# dimmer3.net
KiCad netlist of a schematic drawn in EAGLE
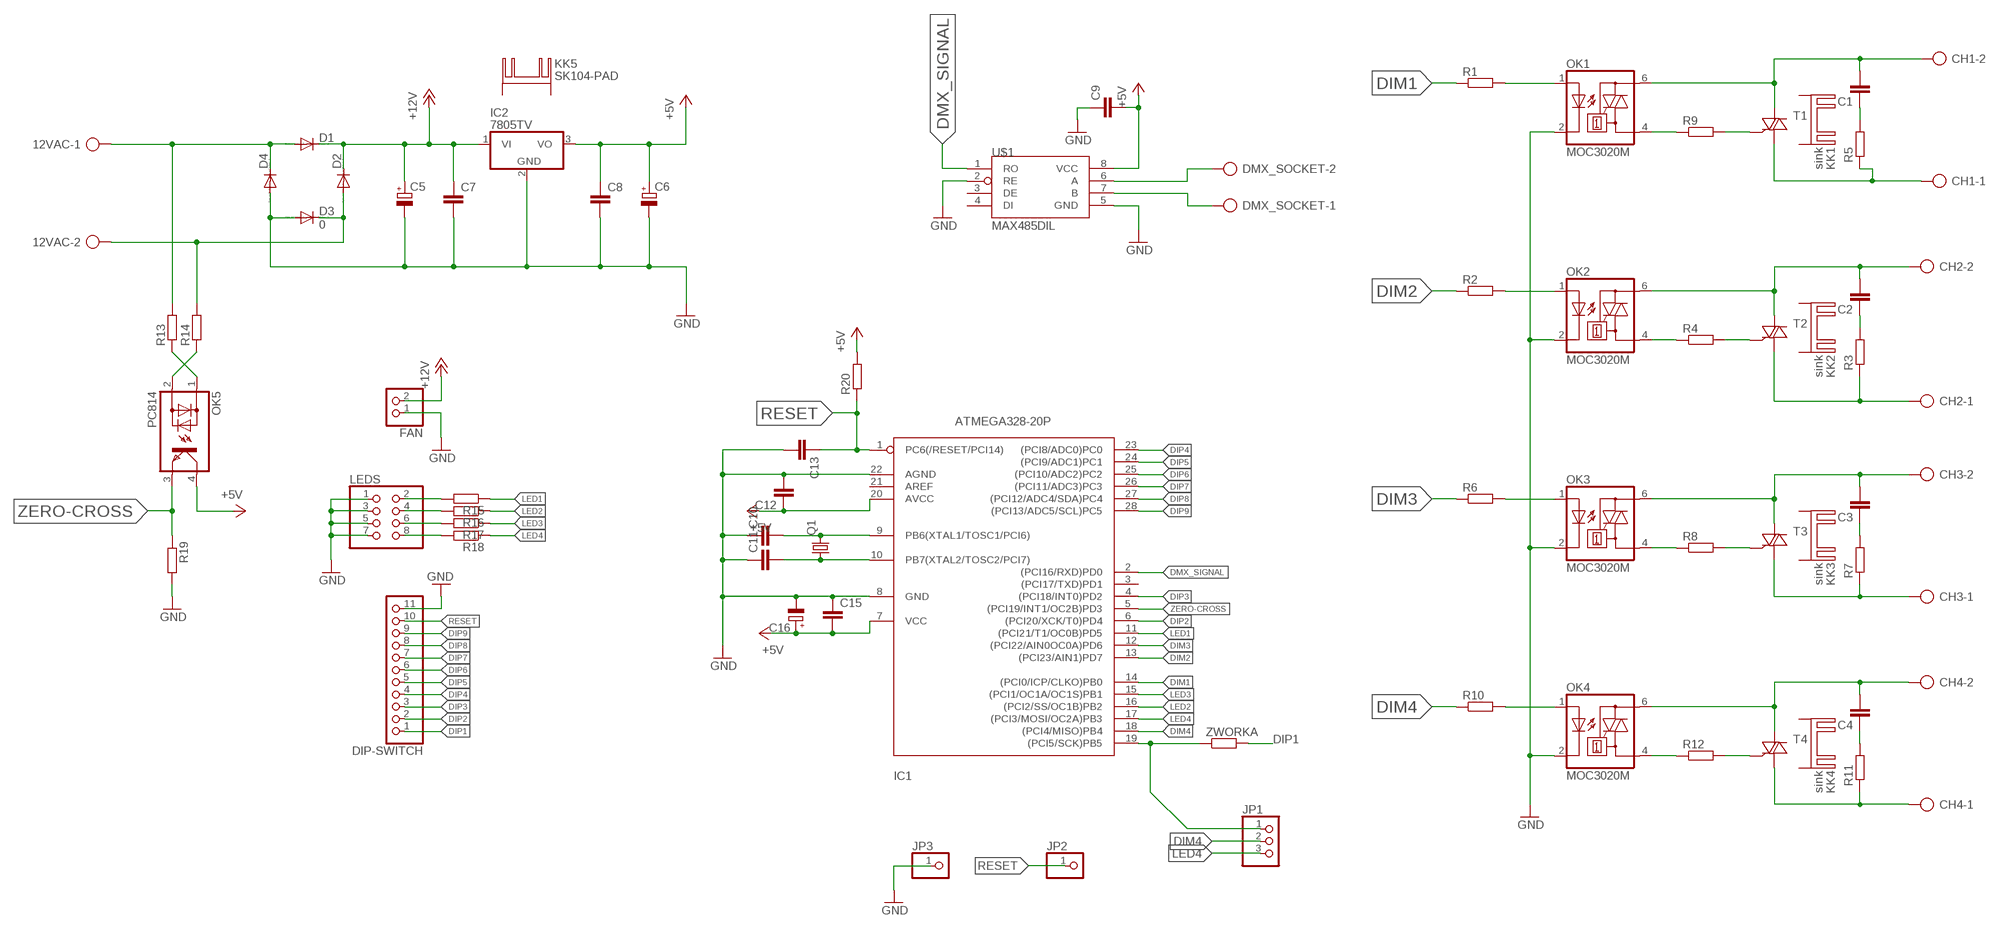
[diagram p0: schematic, sheet 1]

(export (version "E")
  (design (tool "Eeschema 10.0.6"))
  (components
    (comp (ref "12VAC")
      (value "AK500/2")
      (footprint "eagle-import:AK500_2")
      (libsource (lib "eagle-import") (part "AK500/2"))
    )
    (comp (ref "C1")
      (value "C-EU102-054X133")
      (footprint "eagle-import:C102-054X133")
      (libsource (lib "eagle-import") (part "C-EU102-054X133"))
    )
    (comp (ref "C2")
      (value "C-EU102-054X133")
      (footprint "eagle-import:C102-054X133")
      (libsource (lib "eagle-import") (part "C-EU102-054X133"))
    )
    (comp (ref "C3")
      (value "C-EU102-054X133")
      (footprint "eagle-import:C102-054X133")
      (libsource (lib "eagle-import") (part "C-EU102-054X133"))
    )
    (comp (ref "C4")
      (value "C-EU102-054X133")
      (footprint "eagle-import:C102-054X133")
      (libsource (lib "eagle-import") (part "C-EU102-054X133"))
    )
    (comp (ref "C5")
      (value "CPOL-EUE5-13")
      (footprint "eagle-import:E5-13")
      (libsource (lib "eagle-import") (part "CPOL-EUE5-13"))
    )
    (comp (ref "C6")
      (value "CPOL-EUE2.5-7")
      (footprint "eagle-import:E2,5-7")
      (libsource (lib "eagle-import") (part "CPOL-EUE2.5-7"))
    )
    (comp (ref "C7")
      (value "C-EU050-024X044")
      (footprint "eagle-import:C050-024X044")
      (libsource (lib "eagle-import") (part "C-EU050-024X044"))
    )
    (comp (ref "C8")
      (value "C-EU050-024X044")
      (footprint "eagle-import:C050-024X044")
      (libsource (lib "eagle-import") (part "C-EU050-024X044"))
    )
    (comp (ref "C9")
      (value "C-EU050-024X044")
      (footprint "eagle-import:C050-024X044")
      (libsource (lib "eagle-import") (part "C-EU050-024X044"))
    )
    (comp (ref "C10")
      (value "C-EU050-024X044")
      (footprint "eagle-import:C050-024X044")
      (libsource (lib "eagle-import") (part "C-EU050-024X044"))
    )
    (comp (ref "C11")
      (value "C-EU050-024X044")
      (footprint "eagle-import:C050-024X044")
      (libsource (lib "eagle-import") (part "C-EU050-024X044"))
    )
    (comp (ref "C12")
      (value "C-EU050-024X044")
      (footprint "eagle-import:C050-024X044")
      (libsource (lib "eagle-import") (part "C-EU050-024X044"))
    )
    (comp (ref "C13")
      (value "C-EU050-024X044")
      (footprint "eagle-import:C050-024X044")
      (libsource (lib "eagle-import") (part "C-EU050-024X044"))
    )
    (comp (ref "C15")
      (value "C-EU050-024X044")
      (footprint "eagle-import:C050-024X044")
      (libsource (lib "eagle-import") (part "C-EU050-024X044"))
    )
    (comp (ref "C16")
      (value "CPOL-EUE2,5-6E")
      (footprint "eagle-import:E2,5-6E")
      (libsource (lib "eagle-import") (part "CPOL-EUE2,5-6E"))
    )
    (comp (ref "CH1")
      (value "AK500/2")
      (footprint "eagle-import:AK500_2")
      (libsource (lib "eagle-import") (part "AK500/2"))
    )
    (comp (ref "CH2")
      (value "AK500/2")
      (footprint "eagle-import:AK500_2")
      (libsource (lib "eagle-import") (part "AK500/2"))
    )
    (comp (ref "CH3")
      (value "AK500/2")
      (footprint "eagle-import:AK500_2")
      (libsource (lib "eagle-import") (part "AK500/2"))
    )
    (comp (ref "CH4")
      (value "AK500/2")
      (footprint "eagle-import:AK500_2")
      (libsource (lib "eagle-import") (part "AK500/2"))
    )
    (comp (ref "D1")
      (value "1N4004")
      (footprint "eagle-import:DO41-10")
      (libsource (lib "eagle-import") (part "1N4004"))
    )
    (comp (ref "D2")
      (value "1N4004")
      (footprint "eagle-import:DO41-10")
      (libsource (lib "eagle-import") (part "1N4004"))
    )
    (comp (ref "D3")
      (value "0")
      (footprint "eagle-import:DO41-10")
      (libsource (lib "eagle-import") (part "1N4004"))
    )
    (comp (ref "D4")
      (value "1N4004")
      (footprint "eagle-import:DO41-10")
      (libsource (lib "eagle-import") (part "1N4004"))
    )
    (comp (ref "DIP-SWITCH")
      (value "PINHD-1X11")
      (footprint "eagle-import:1X11")
      (libsource (lib "eagle-import") (part "PINHD-1X11"))
    )
    (comp (ref "DMX_SOCKET")
      (value "AK500/2")
      (footprint "eagle-import:AK500_2")
      (libsource (lib "eagle-import") (part "AK500/2"))
    )
    (comp (ref "FAN")
      (value "PINHD-1X2")
      (footprint "eagle-import:1X02")
      (libsource (lib "eagle-import") (part "PINHD-1X2"))
    )
    (comp (ref "IC1")
      (value "ATMEGA328-20P")
      (footprint "eagle-import:DIL28-3")
      (libsource (lib "eagle-import") (part "ATMEGA328P-20"))
    )
    (comp (ref "IC2")
      (value "7805TV")
      (footprint "eagle-import:TO220V")
      (libsource (lib "eagle-import") (part "78TV05"))
    )
    (comp (ref "JP1")
      (value "PINHD-1X3")
      (footprint "eagle-import:1X03")
      (libsource (lib "eagle-import") (part "PINHD-1X3"))
    )
    (comp (ref "JP2")
      (value "PINHD-1X1")
      (footprint "eagle-import:1X01")
      (libsource (lib "eagle-import") (part "PINHD-1X1"))
    )
    (comp (ref "JP3")
      (value "PINHD-1X1")
      (footprint "eagle-import:1X01")
      (libsource (lib "eagle-import") (part "PINHD-1X1"))
    )
    (comp (ref "KK1")
      (value "sink")
      (footprint "eagle-import:SK104-PAD")
      (libsource (lib "eagle-import") (part "SK104-PAD"))
    )
    (comp (ref "KK2")
      (value "sink")
      (footprint "eagle-import:SK104-PAD")
      (libsource (lib "eagle-import") (part "SK104-PAD"))
    )
    (comp (ref "KK3")
      (value "sink")
      (footprint "eagle-import:SK104-PAD")
      (libsource (lib "eagle-import") (part "SK104-PAD"))
    )
    (comp (ref "KK4")
      (value "sink")
      (footprint "eagle-import:SK104-PAD")
      (libsource (lib "eagle-import") (part "SK104-PAD"))
    )
    (comp (ref "KK5")
      (value "SK104-PAD")
      (footprint "eagle-import:SK104-PAD")
      (libsource (lib "eagle-import") (part "SK104-PAD"))
    )
    (comp (ref "LEDS")
      (value "PINHD-2X4")
      (footprint "eagle-import:2X04")
      (libsource (lib "eagle-import") (part "PINHD-2X4"))
    )
    (comp (ref "OK1")
      (value "MOC3020M")
      (footprint "eagle-import:DIL06")
      (fields (field (name "MF") "FAIRCHILD SEMICONDUCTOR") (field (name "MPN") "MOC3020-M"))
      (libsource (lib "eagle-import") (part "MOC30M20"))
    )
    (comp (ref "OK2")
      (value "MOC3020M")
      (footprint "eagle-import:DIL06")
      (fields (field (name "MF") "FAIRCHILD SEMICONDUCTOR") (field (name "MPN") "MOC3020-M"))
      (libsource (lib "eagle-import") (part "MOC30M20"))
    )
    (comp (ref "OK3")
      (value "MOC3020M")
      (footprint "eagle-import:DIL06")
      (fields (field (name "MF") "FAIRCHILD SEMICONDUCTOR") (field (name "MPN") "MOC3020-M"))
      (libsource (lib "eagle-import") (part "MOC30M20"))
    )
    (comp (ref "OK4")
      (value "MOC3020M")
      (footprint "eagle-import:DIL06")
      (fields (field (name "MF") "FAIRCHILD SEMICONDUCTOR") (field (name "MPN") "MOC3020-M"))
      (libsource (lib "eagle-import") (part "MOC30M20"))
    )
    (comp (ref "OK5")
      (value "PC814")
      (footprint "eagle-import:DIL04")
      (libsource (lib "eagle-import") (part "PC814"))
    )
    (comp (ref "Q1")
      (value "CRYSTALHC49U-V")
      (footprint "eagle-import:HC49U-V")
      (libsource (lib "eagle-import") (part "CRYSTALHC49U-V"))
    )
    (comp (ref "R1")
      (value "R-EU_0207/10")
      (footprint "eagle-import:0207_10")
      (libsource (lib "eagle-import") (part "R-EU_0207/10"))
    )
    (comp (ref "R2")
      (value "R-EU_0207/10")
      (footprint "eagle-import:0207_10")
      (libsource (lib "eagle-import") (part "R-EU_0207/10"))
    )
    (comp (ref "R3")
      (value "R-EU_0617/22")
      (footprint "eagle-import:0617_22")
      (libsource (lib "eagle-import") (part "R-EU_0617/22"))
    )
    (comp (ref "R4")
      (value "R-EU_0207/10")
      (footprint "eagle-import:0207_10")
      (libsource (lib "eagle-import") (part "R-EU_0207/10"))
    )
    (comp (ref "R5")
      (value "R-EU_0617/22")
      (footprint "eagle-import:0617_22")
      (libsource (lib "eagle-import") (part "R-EU_0617/22"))
    )
    (comp (ref "R6")
      (value "R-EU_0207/10")
      (footprint "eagle-import:0207_10")
      (libsource (lib "eagle-import") (part "R-EU_0207/10"))
    )
    (comp (ref "R7")
      (value "R-EU_0617/22")
      (footprint "eagle-import:0617_22")
      (libsource (lib "eagle-import") (part "R-EU_0617/22"))
    )
    (comp (ref "R8")
      (value "R-EU_0207/10")
      (footprint "eagle-import:0207_10")
      (libsource (lib "eagle-import") (part "R-EU_0207/10"))
    )
    (comp (ref "R9")
      (value "R-EU_0207/10")
      (footprint "eagle-import:0207_10")
      (libsource (lib "eagle-import") (part "R-EU_0207/10"))
    )
    (comp (ref "R10")
      (value "R-EU_0207/10")
      (footprint "eagle-import:0207_10")
      (libsource (lib "eagle-import") (part "R-EU_0207/10"))
    )
    (comp (ref "R11")
      (value "R-EU_0617/22")
      (footprint "eagle-import:0617_22")
      (libsource (lib "eagle-import") (part "R-EU_0617/22"))
    )
    (comp (ref "R12")
      (value "R-EU_0207/10")
      (footprint "eagle-import:0207_10")
      (libsource (lib "eagle-import") (part "R-EU_0207/10"))
    )
    (comp (ref "R13")
      (value "R-EU_0207/10")
      (footprint "eagle-import:0207_10")
      (libsource (lib "eagle-import") (part "R-EU_0207/10"))
    )
    (comp (ref "R14")
      (value "R-EU_0207/10")
      (footprint "eagle-import:0207_10")
      (libsource (lib "eagle-import") (part "R-EU_0207/10"))
    )
    (comp (ref "R15")
      (value "R-EU_0207/10")
      (footprint "eagle-import:0207_10")
      (libsource (lib "eagle-import") (part "R-EU_0207/10"))
    )
    (comp (ref "R16")
      (value "R-EU_0207/10")
      (footprint "eagle-import:0207_10")
      (libsource (lib "eagle-import") (part "R-EU_0207/10"))
    )
    (comp (ref "R17")
      (value "R-EU_0207/10")
      (footprint "eagle-import:0207_10")
      (libsource (lib "eagle-import") (part "R-EU_0207/10"))
    )
    (comp (ref "R18")
      (value "R-EU_0207/10")
      (footprint "eagle-import:0207_10")
      (libsource (lib "eagle-import") (part "R-EU_0207/10"))
    )
    (comp (ref "R19")
      (value "R-EU_0207/10")
      (footprint "eagle-import:0207_10")
      (libsource (lib "eagle-import") (part "R-EU_0207/10"))
    )
    (comp (ref "R20")
      (value "R-EU_0207/10")
      (footprint "eagle-import:0207_10")
      (libsource (lib "eagle-import") (part "R-EU_0207/10"))
    )
    (comp (ref "T1")
      (value "BT138-DSH")
      (footprint "eagle-import:TO220DSH")
      (libsource (lib "eagle-import") (part "BT138-DSH"))
    )
    (comp (ref "T2")
      (value "BT138-DSH")
      (footprint "eagle-import:TO220DSH")
      (libsource (lib "eagle-import") (part "BT138-DSH"))
    )
    (comp (ref "T3")
      (value "BT138-DSH")
      (footprint "eagle-import:TO220DSH")
      (libsource (lib "eagle-import") (part "BT138-DSH"))
    )
    (comp (ref "T4")
      (value "BT138-DSH")
      (footprint "eagle-import:TO220DSH")
      (libsource (lib "eagle-import") (part "BT138-DSH"))
    )
    (comp (ref "U$1")
      (value "MAX485DIL")
      (footprint "eagle-import:DIL08")
      (libsource (lib "eagle-import") (part "MAX485DIL"))
    )
    (comp (ref "ZWORKA")
      (value "R-EU_0204/7")
      (footprint "eagle-import:0204_7")
      (libsource (lib "eagle-import") (part "R-EU_0204/7"))
    )
  )
  (nets
    (net (code "1") (name "+5V") (class "Default")
      (node (ref "C12") (pin "1") (pinfunction "1_1") (pintype "passive"))
      (node (ref "C15") (pin "2") (pinfunction "2_2") (pintype "passive"))
      (node (ref "C16") (pin "+") (pinfunction "+_+") (pintype "passive"))
      (node (ref "C6") (pin "+") (pinfunction "+_+") (pintype "passive"))
      (node (ref "C8") (pin "1") (pinfunction "1_1") (pintype "passive"))
      (node (ref "C9") (pin "2") (pinfunction "2_2") (pintype "passive"))
      (node (ref "IC1") (pin "20") (pinfunction "AVCC_20") (pintype "bidirectional"))
      (node (ref "IC1") (pin "7") (pinfunction "VCC_7") (pintype "bidirectional"))
      (node (ref "IC2") (pin "3") (pinfunction "VO_3") (pintype "passive"))
      (node (ref "OK5") (pin "4") (pinfunction "C_4") (pintype "passive"))
      (node (ref "R20") (pin "2") (pinfunction "2_2") (pintype "passive"))
      (node (ref "U$1") (pin "8") (pinfunction "VCC_8") (pintype "bidirectional"))
    )
    (net (code "2") (name "+12V") (class "Default")
      (node (ref "C5") (pin "+") (pinfunction "+_+") (pintype "passive"))
      (node (ref "C7") (pin "1") (pinfunction "1_1") (pintype "passive"))
      (node (ref "D1") (pin "C") (pinfunction "C_C") (pintype "passive"))
      (node (ref "D2") (pin "C") (pinfunction "C_C") (pintype "passive"))
      (node (ref "FAN") (pin "2") (pinfunction "2_2") (pintype "passive"))
      (node (ref "IC2") (pin "1") (pinfunction "VI_1") (pintype "input"))
    )
    (net (code "3") (name "DIM1") (class "Default")
      (node (ref "IC1") (pin "14") (pinfunction "(PCI0/ICP/CLKO)PB0_14") (pintype "bidirectional"))
      (node (ref "R1") (pin "1") (pinfunction "1_1") (pintype "passive"))
    )
    (net (code "4") (name "DIM2") (class "Default")
      (node (ref "IC1") (pin "13") (pinfunction "(PCI23/AIN1)PD7_13") (pintype "bidirectional"))
      (node (ref "R2") (pin "1") (pinfunction "1_1") (pintype "passive"))
    )
    (net (code "5") (name "DIM3") (class "Default")
      (node (ref "IC1") (pin "12") (pinfunction "(PCI22/AIN0OC0A)PD6_12") (pintype "bidirectional"))
      (node (ref "R6") (pin "1") (pinfunction "1_1") (pintype "passive"))
    )
    (net (code "6") (name "DIM4") (class "Default")
      (node (ref "IC1") (pin "18") (pinfunction "(PCI4/MISO)PB4_18") (pintype "bidirectional"))
      (node (ref "JP1") (pin "2") (pinfunction "2_2") (pintype "passive"))
      (node (ref "R10") (pin "1") (pinfunction "1_1") (pintype "passive"))
    )
    (net (code "7") (name "DIP1") (class "Default")
      (node (ref "DIP-SWITCH") (pin "1") (pinfunction "1_1") (pintype "passive"))
      (node (ref "ZWORKA") (pin "2") (pinfunction "2_2") (pintype "passive"))
    )
    (net (code "8") (name "DIP2") (class "Default")
      (node (ref "DIP-SWITCH") (pin "2") (pinfunction "2_2") (pintype "passive"))
      (node (ref "IC1") (pin "6") (pinfunction "(PCI20/XCK/T0)PD4_6") (pintype "bidirectional"))
    )
    (net (code "9") (name "DIP3") (class "Default")
      (node (ref "DIP-SWITCH") (pin "3") (pinfunction "3_3") (pintype "passive"))
      (node (ref "IC1") (pin "4") (pinfunction "(PCI18/INT0)PD2_4") (pintype "bidirectional"))
    )
    (net (code "10") (name "DIP4") (class "Default")
      (node (ref "DIP-SWITCH") (pin "4") (pinfunction "4_4") (pintype "passive"))
      (node (ref "IC1") (pin "23") (pinfunction "(PCI8/ADC0)PC0_23") (pintype "bidirectional"))
    )
    (net (code "11") (name "DIP5") (class "Default")
      (node (ref "DIP-SWITCH") (pin "5") (pinfunction "5_5") (pintype "passive"))
      (node (ref "IC1") (pin "24") (pinfunction "(PCI9/ADC1)PC1_24") (pintype "bidirectional"))
    )
    (net (code "12") (name "DIP6") (class "Default")
      (node (ref "DIP-SWITCH") (pin "6") (pinfunction "6_6") (pintype "passive"))
      (node (ref "IC1") (pin "25") (pinfunction "(PCI10/ADC2)PC2_25") (pintype "bidirectional"))
    )
    (net (code "13") (name "DIP7") (class "Default")
      (node (ref "DIP-SWITCH") (pin "7") (pinfunction "7_7") (pintype "passive"))
      (node (ref "IC1") (pin "26") (pinfunction "(PCI11/ADC3)PC3_26") (pintype "bidirectional"))
    )
    (net (code "14") (name "DIP8") (class "Default")
      (node (ref "DIP-SWITCH") (pin "8") (pinfunction "8_8") (pintype "passive"))
      (node (ref "IC1") (pin "27") (pinfunction "(PCI12/ADC4/SDA)PC4_27") (pintype "bidirectional"))
    )
    (net (code "15") (name "DIP9") (class "Default")
      (node (ref "DIP-SWITCH") (pin "9") (pinfunction "9_9") (pintype "passive"))
      (node (ref "IC1") (pin "28") (pinfunction "(PCI13/ADC5/SCL)PC5_28") (pintype "bidirectional"))
    )
    (net (code "16") (name "DMX_SIGNAL") (class "Default")
      (node (ref "IC1") (pin "2") (pinfunction "(PCI16/RXD)PD0_2") (pintype "bidirectional"))
      (node (ref "U$1") (pin "1") (pinfunction "RO_1") (pintype "bidirectional"))
    )
    (net (code "17") (name "GND") (class "Default")
      (node (ref "C10") (pin "1") (pinfunction "1_1") (pintype "passive"))
      (node (ref "C11") (pin "1") (pinfunction "1_1") (pintype "passive"))
      (node (ref "C12") (pin "2") (pinfunction "2_2") (pintype "passive"))
      (node (ref "C13") (pin "2") (pinfunction "2_2") (pintype "passive"))
      (node (ref "C15") (pin "1") (pinfunction "1_1") (pintype "passive"))
      (node (ref "C16") (pin "-") (pinfunction "-_-") (pintype "passive"))
      (node (ref "C5") (pin "-") (pinfunction "-_-") (pintype "passive"))
      (node (ref "C6") (pin "-") (pinfunction "-_-") (pintype "passive"))
      (node (ref "C7") (pin "2") (pinfunction "2_2") (pintype "passive"))
      (node (ref "C8") (pin "2") (pinfunction "2_2") (pintype "passive"))
      (node (ref "C9") (pin "1") (pinfunction "1_1") (pintype "passive"))
      (node (ref "D3") (pin "A") (pinfunction "A_A") (pintype "passive"))
      (node (ref "D4") (pin "A") (pinfunction "A_A") (pintype "passive"))
      (node (ref "DIP-SWITCH") (pin "11") (pinfunction "11_11") (pintype "passive"))
      (node (ref "FAN") (pin "1") (pinfunction "1_1") (pintype "passive"))
      (node (ref "IC1") (pin "22") (pinfunction "AGND_22") (pintype "bidirectional"))
      (node (ref "IC1") (pin "8") (pinfunction "GND_8") (pintype "bidirectional"))
      (node (ref "IC2") (pin "2") (pinfunction "GND_2") (pintype "passive"))
      (node (ref "JP3") (pin "1") (pinfunction "1_1") (pintype "passive"))
      (node (ref "LEDS") (pin "1") (pinfunction "1_1") (pintype "passive"))
      (node (ref "LEDS") (pin "3") (pinfunction "3_3") (pintype "passive"))
      (node (ref "LEDS") (pin "5") (pinfunction "5_5") (pintype "passive"))
      (node (ref "LEDS") (pin "7") (pinfunction "7_7") (pintype "passive"))
      (node (ref "OK1") (pin "2") (pinfunction "C_2") (pintype "passive"))
      (node (ref "OK2") (pin "2") (pinfunction "C_2") (pintype "passive"))
      (node (ref "OK3") (pin "2") (pinfunction "C_2") (pintype "passive"))
      (node (ref "OK4") (pin "2") (pinfunction "C_2") (pintype "passive"))
      (node (ref "R19") (pin "2") (pinfunction "2_2") (pintype "passive"))
      (node (ref "U$1") (pin "2") (pinfunction "RE_2") (pintype "bidirectional"))
      (node (ref "U$1") (pin "5") (pinfunction "GND_5") (pintype "bidirectional"))
    )
    (net (code "18") (name "LED1") (class "Default")
      (node (ref "IC1") (pin "11") (pinfunction "(PCI21/T1/OC0B)PD5_11") (pintype "bidirectional"))
      (node (ref "R15") (pin "1") (pinfunction "1_1") (pintype "passive"))
    )
    (net (code "19") (name "LED2") (class "Default")
      (node (ref "IC1") (pin "16") (pinfunction "(PCI2/SS/OC1B)PB2_16") (pintype "bidirectional"))
      (node (ref "R16") (pin "1") (pinfunction "1_1") (pintype "passive"))
    )
    (net (code "20") (name "LED3") (class "Default")
      (node (ref "IC1") (pin "15") (pinfunction "(PCI1/OC1A/OC1S)PB1_15") (pintype "bidirectional"))
      (node (ref "R17") (pin "1") (pinfunction "1_1") (pintype "passive"))
    )
    (net (code "21") (name "LED4") (class "Default")
      (node (ref "IC1") (pin "17") (pinfunction "(PCI3/MOSI/OC2A)PB3_17") (pintype "bidirectional"))
      (node (ref "JP1") (pin "3") (pinfunction "3_3") (pintype "passive"))
      (node (ref "R18") (pin "1") (pinfunction "1_1") (pintype "passive"))
    )
    (net (code "22") (name "Net-(12VACA-KL)") (class "Default")
      (node (ref "12VAC") (pin "1") (pinfunction "KL_1") (pintype "passive"))
      (node (ref "D1") (pin "A") (pinfunction "A_A") (pintype "passive"))
      (node (ref "D4") (pin "C") (pinfunction "C_C") (pintype "passive"))
      (node (ref "R13") (pin "2") (pinfunction "2_2") (pintype "passive"))
    )
    (net (code "23") (name "Net-(12VACB-KL)") (class "Default")
      (node (ref "12VAC") (pin "2") (pinfunction "KL_2") (pintype "passive"))
      (node (ref "D2") (pin "A") (pinfunction "A_A") (pintype "passive"))
      (node (ref "D3") (pin "C") (pinfunction "C_C") (pintype "passive"))
      (node (ref "R14") (pin "2") (pinfunction "2_2") (pintype "passive"))
    )
    (net (code "24") (name "Net-(C1-Pad1)") (class "Default")
      (node (ref "C1") (pin "1") (pinfunction "1_1") (pintype "passive"))
      (node (ref "R5") (pin "2") (pinfunction "2_2") (pintype "passive"))
    )
    (net (code "25") (name "Net-(C2-Pad1)") (class "Default")
      (node (ref "C2") (pin "1") (pinfunction "1_1") (pintype "passive"))
      (node (ref "R3") (pin "2") (pinfunction "2_2") (pintype "passive"))
    )
    (net (code "26") (name "Net-(C3-Pad1)") (class "Default")
      (node (ref "C3") (pin "1") (pinfunction "1_1") (pintype "passive"))
      (node (ref "R7") (pin "2") (pinfunction "2_2") (pintype "passive"))
    )
    (net (code "27") (name "Net-(C4-Pad1)") (class "Default")
      (node (ref "C4") (pin "1") (pinfunction "1_1") (pintype "passive"))
      (node (ref "R11") (pin "2") (pinfunction "2_2") (pintype "passive"))
    )
    (net (code "28") (name "Net-(CH1A-KL)") (class "Default")
      (node (ref "CH1") (pin "1") (pinfunction "KL_1") (pintype "passive"))
      (node (ref "R5") (pin "1") (pinfunction "1_1") (pintype "passive"))
      (node (ref "T1") (pin "A1") (pinfunction "A1_A1") (pintype "passive"))
    )
    (net (code "29") (name "Net-(CH1B-KL)") (class "Default")
      (node (ref "C1") (pin "2") (pinfunction "2_2") (pintype "passive"))
      (node (ref "CH1") (pin "2") (pinfunction "KL_2") (pintype "passive"))
      (node (ref "OK1") (pin "6") (pinfunction "A2_6") (pintype "passive"))
      (node (ref "T1") (pin "A2") (pinfunction "A2_A2") (pintype "passive"))
    )
    (net (code "30") (name "Net-(CH2A-KL)") (class "Default")
      (node (ref "CH2") (pin "1") (pinfunction "KL_1") (pintype "passive"))
      (node (ref "R3") (pin "1") (pinfunction "1_1") (pintype "passive"))
      (node (ref "T2") (pin "A1") (pinfunction "A1_A1") (pintype "passive"))
    )
    (net (code "31") (name "Net-(CH2B-KL)") (class "Default")
      (node (ref "C2") (pin "2") (pinfunction "2_2") (pintype "passive"))
      (node (ref "CH2") (pin "2") (pinfunction "KL_2") (pintype "passive"))
      (node (ref "OK2") (pin "6") (pinfunction "A2_6") (pintype "passive"))
      (node (ref "T2") (pin "A2") (pinfunction "A2_A2") (pintype "passive"))
    )
    (net (code "32") (name "Net-(CH3A-KL)") (class "Default")
      (node (ref "CH3") (pin "1") (pinfunction "KL_1") (pintype "passive"))
      (node (ref "R7") (pin "1") (pinfunction "1_1") (pintype "passive"))
      (node (ref "T3") (pin "A1") (pinfunction "A1_A1") (pintype "passive"))
    )
    (net (code "33") (name "Net-(CH3B-KL)") (class "Default")
      (node (ref "C3") (pin "2") (pinfunction "2_2") (pintype "passive"))
      (node (ref "CH3") (pin "2") (pinfunction "KL_2") (pintype "passive"))
      (node (ref "OK3") (pin "6") (pinfunction "A2_6") (pintype "passive"))
      (node (ref "T3") (pin "A2") (pinfunction "A2_A2") (pintype "passive"))
    )
    (net (code "34") (name "Net-(CH4A-KL)") (class "Default")
      (node (ref "CH4") (pin "1") (pinfunction "KL_1") (pintype "passive"))
      (node (ref "R11") (pin "1") (pinfunction "1_1") (pintype "passive"))
      (node (ref "T4") (pin "A1") (pinfunction "A1_A1") (pintype "passive"))
    )
    (net (code "35") (name "Net-(CH4B-KL)") (class "Default")
      (node (ref "C4") (pin "2") (pinfunction "2_2") (pintype "passive"))
      (node (ref "CH4") (pin "2") (pinfunction "KL_2") (pintype "passive"))
      (node (ref "OK4") (pin "6") (pinfunction "A2_6") (pintype "passive"))
      (node (ref "T4") (pin "A2") (pinfunction "A2_A2") (pintype "passive"))
    )
    (net (code "36") (name "Net-(DMX_SOCKETA-KL)") (class "Default")
      (node (ref "DMX_SOCKET") (pin "1") (pinfunction "KL_1") (pintype "passive"))
      (node (ref "U$1") (pin "7") (pinfunction "B_7") (pintype "bidirectional"))
    )
    (net (code "37") (name "Net-(DMX_SOCKETB-KL)") (class "Default")
      (node (ref "DMX_SOCKET") (pin "2") (pinfunction "KL_2") (pintype "passive"))
      (node (ref "U$1") (pin "6") (pinfunction "A_6") (pintype "bidirectional"))
    )
    (net (code "38") (name "Net-(IC1-(PCI5{slash}SCK)PB5)") (class "Default")
      (node (ref "IC1") (pin "19") (pinfunction "(PCI5/SCK)PB5_19") (pintype "bidirectional"))
      (node (ref "JP1") (pin "1") (pinfunction "1_1") (pintype "passive"))
      (node (ref "ZWORKA") (pin "1") (pinfunction "1_1") (pintype "passive"))
    )
    (net (code "39") (name "Net-(IC1-PB6(XTAL1{slash}TOSC1{slash}PCI6))") (class "Default")
      (node (ref "C10") (pin "2") (pinfunction "2_2") (pintype "passive"))
      (node (ref "IC1") (pin "9") (pinfunction "PB6(XTAL1/TOSC1/PCI6)_9") (pintype "bidirectional"))
      (node (ref "Q1") (pin "2") (pinfunction "2_2") (pintype "passive"))
    )
    (net (code "40") (name "Net-(IC1-PB7(XTAL2{slash}TOSC2{slash}PCI7))") (class "Default")
      (node (ref "C11") (pin "2") (pinfunction "2_2") (pintype "passive"))
      (node (ref "IC1") (pin "10") (pinfunction "PB7(XTAL2/TOSC2/PCI7)_10") (pintype "bidirectional"))
      (node (ref "Q1") (pin "1") (pinfunction "1_1") (pintype "passive"))
    )
    (net (code "41") (name "Net-(LEDS-Pad2)") (class "Default")
      (node (ref "LEDS") (pin "2") (pinfunction "2_2") (pintype "passive"))
      (node (ref "R15") (pin "2") (pinfunction "2_2") (pintype "passive"))
    )
    (net (code "42") (name "Net-(LEDS-Pad4)") (class "Default")
      (node (ref "LEDS") (pin "4") (pinfunction "4_4") (pintype "passive"))
      (node (ref "R16") (pin "2") (pinfunction "2_2") (pintype "passive"))
    )
    (net (code "43") (name "Net-(LEDS-Pad6)") (class "Default")
      (node (ref "LEDS") (pin "6") (pinfunction "6_6") (pintype "passive"))
      (node (ref "R17") (pin "2") (pinfunction "2_2") (pintype "passive"))
    )
    (net (code "44") (name "Net-(LEDS-Pad8)") (class "Default")
      (node (ref "LEDS") (pin "8") (pinfunction "8_8") (pintype "passive"))
      (node (ref "R18") (pin "2") (pinfunction "2_2") (pintype "passive"))
    )
    (net (code "45") (name "Net-(OK1-A)") (class "Default")
      (node (ref "OK1") (pin "1") (pinfunction "A_1") (pintype "passive"))
      (node (ref "R1") (pin "2") (pinfunction "2_2") (pintype "passive"))
    )
    (net (code "46") (name "Net-(OK1-A1)") (class "Default")
      (node (ref "OK1") (pin "4") (pinfunction "A1_4") (pintype "passive"))
      (node (ref "R9") (pin "1") (pinfunction "1_1") (pintype "passive"))
    )
    (net (code "47") (name "Net-(OK2-A)") (class "Default")
      (node (ref "OK2") (pin "1") (pinfunction "A_1") (pintype "passive"))
      (node (ref "R2") (pin "2") (pinfunction "2_2") (pintype "passive"))
    )
    (net (code "48") (name "Net-(OK2-A1)") (class "Default")
      (node (ref "OK2") (pin "4") (pinfunction "A1_4") (pintype "passive"))
      (node (ref "R4") (pin "1") (pinfunction "1_1") (pintype "passive"))
    )
    (net (code "49") (name "Net-(OK3-A)") (class "Default")
      (node (ref "OK3") (pin "1") (pinfunction "A_1") (pintype "passive"))
      (node (ref "R6") (pin "2") (pinfunction "2_2") (pintype "passive"))
    )
    (net (code "50") (name "Net-(OK3-A1)") (class "Default")
      (node (ref "OK3") (pin "4") (pinfunction "A1_4") (pintype "passive"))
      (node (ref "R8") (pin "1") (pinfunction "1_1") (pintype "passive"))
    )
    (net (code "51") (name "Net-(OK4-A)") (class "Default")
      (node (ref "OK4") (pin "1") (pinfunction "A_1") (pintype "passive"))
      (node (ref "R10") (pin "2") (pinfunction "2_2") (pintype "passive"))
    )
    (net (code "52") (name "Net-(OK4-A1)") (class "Default")
      (node (ref "OK4") (pin "4") (pinfunction "A1_4") (pintype "passive"))
      (node (ref "R12") (pin "1") (pinfunction "1_1") (pintype "passive"))
    )
    (net (code "53") (name "Net-(OK5-AC1)") (class "Default")
      (node (ref "OK5") (pin "1") (pinfunction "AC1_1") (pintype "passive"))
      (node (ref "R13") (pin "1") (pinfunction "1_1") (pintype "passive"))
    )
    (net (code "54") (name "Net-(OK5-AC2)") (class "Default")
      (node (ref "OK5") (pin "2") (pinfunction "AC2_2") (pintype "passive"))
      (node (ref "R14") (pin "1") (pinfunction "1_1") (pintype "passive"))
    )
    (net (code "55") (name "Net-(R4-Pad2)") (class "Default")
      (node (ref "R4") (pin "2") (pinfunction "2_2") (pintype "passive"))
      (node (ref "T2") (pin "G") (pinfunction "G_G") (pintype "passive"))
    )
    (net (code "56") (name "Net-(R8-Pad2)") (class "Default")
      (node (ref "R8") (pin "2") (pinfunction "2_2") (pintype "passive"))
      (node (ref "T3") (pin "G") (pinfunction "G_G") (pintype "passive"))
    )
    (net (code "57") (name "Net-(R9-Pad2)") (class "Default")
      (node (ref "R9") (pin "2") (pinfunction "2_2") (pintype "passive"))
      (node (ref "T1") (pin "G") (pinfunction "G_G") (pintype "passive"))
    )
    (net (code "58") (name "Net-(R12-Pad2)") (class "Default")
      (node (ref "R12") (pin "2") (pinfunction "2_2") (pintype "passive"))
      (node (ref "T4") (pin "G") (pinfunction "G_G") (pintype "passive"))
    )
    (net (code "59") (name "RESET") (class "Default")
      (node (ref "C13") (pin "1") (pinfunction "1_1") (pintype "passive"))
      (node (ref "DIP-SWITCH") (pin "10") (pinfunction "10_10") (pintype "passive"))
      (node (ref "IC1") (pin "1") (pinfunction "PC6(/RESET/PCI14)_1") (pintype "bidirectional"))
      (node (ref "JP2") (pin "1") (pinfunction "1_1") (pintype "passive"))
      (node (ref "R20") (pin "1") (pinfunction "1_1") (pintype "passive"))
    )
    (net (code "60") (name "ZERO-CROSS") (class "Default")
      (node (ref "IC1") (pin "5") (pinfunction "(PCI19/INT1/OC2B)PD3_5") (pintype "bidirectional"))
      (node (ref "OK5") (pin "3") (pinfunction "E_3") (pintype "passive"))
      (node (ref "R19") (pin "1") (pinfunction "1_1") (pintype "passive"))
    )
    (net (code "61") (name "unconnected-(IC1-(PCI17{slash}TXD)PD1-Pad3)") (class "Default")
      (node (ref "IC1") (pin "3") (pinfunction "(PCI17/TXD)PD1_3") (pintype "bidirectional"))
    )
    (net (code "62") (name "unconnected-(IC1-AREF-Pad21)") (class "Default")
      (node (ref "IC1") (pin "21") (pinfunction "AREF_21") (pintype "bidirectional"))
    )
    (net (code "63") (name "unconnected-(KK1-K-PadK1)") (class "Default")
      (node (ref "KK1") (pin "K1") (pinfunction "K_K1") (pintype "passive"))
    )
    (net (code "64") (name "unconnected-(KK1-K-PadK2)") (class "Default")
      (node (ref "KK1") (pin "K2") (pinfunction "K_K2") (pintype "passive"))
    )
    (net (code "65") (name "unconnected-(KK2-K-PadK1)") (class "Default")
      (node (ref "KK2") (pin "K1") (pinfunction "K_K1") (pintype "passive"))
    )
    (net (code "66") (name "unconnected-(KK2-K-PadK2)") (class "Default")
      (node (ref "KK2") (pin "K2") (pinfunction "K_K2") (pintype "passive"))
    )
    (net (code "67") (name "unconnected-(KK3-K-PadK1)") (class "Default")
      (node (ref "KK3") (pin "K1") (pinfunction "K_K1") (pintype "passive"))
    )
    (net (code "68") (name "unconnected-(KK3-K-PadK2)") (class "Default")
      (node (ref "KK3") (pin "K2") (pinfunction "K_K2") (pintype "passive"))
    )
    (net (code "69") (name "unconnected-(KK4-K-PadK1)") (class "Default")
      (node (ref "KK4") (pin "K1") (pinfunction "K_K1") (pintype "passive"))
    )
    (net (code "70") (name "unconnected-(KK4-K-PadK2)") (class "Default")
      (node (ref "KK4") (pin "K2") (pinfunction "K_K2") (pintype "passive"))
    )
    (net (code "71") (name "unconnected-(KK5-K-PadK1)") (class "Default")
      (node (ref "KK5") (pin "K1") (pinfunction "K_K1") (pintype "passive"))
    )
    (net (code "72") (name "unconnected-(KK5-K-PadK2)") (class "Default")
      (node (ref "KK5") (pin "K2") (pinfunction "K_K2") (pintype "passive"))
    )
    (net (code "73") (name "unconnected-(U$1-DE-Pad3)") (class "Default")
      (node (ref "U$1") (pin "3") (pinfunction "DE_3") (pintype "bidirectional"))
    )
    (net (code "74") (name "unconnected-(U$1-DI-Pad4)") (class "Default")
      (node (ref "U$1") (pin "4") (pinfunction "DI_4") (pintype "bidirectional"))
    )
  )
)
